# Sheet1.net
KiCad netlist of a schematic drawn in Altium Designer
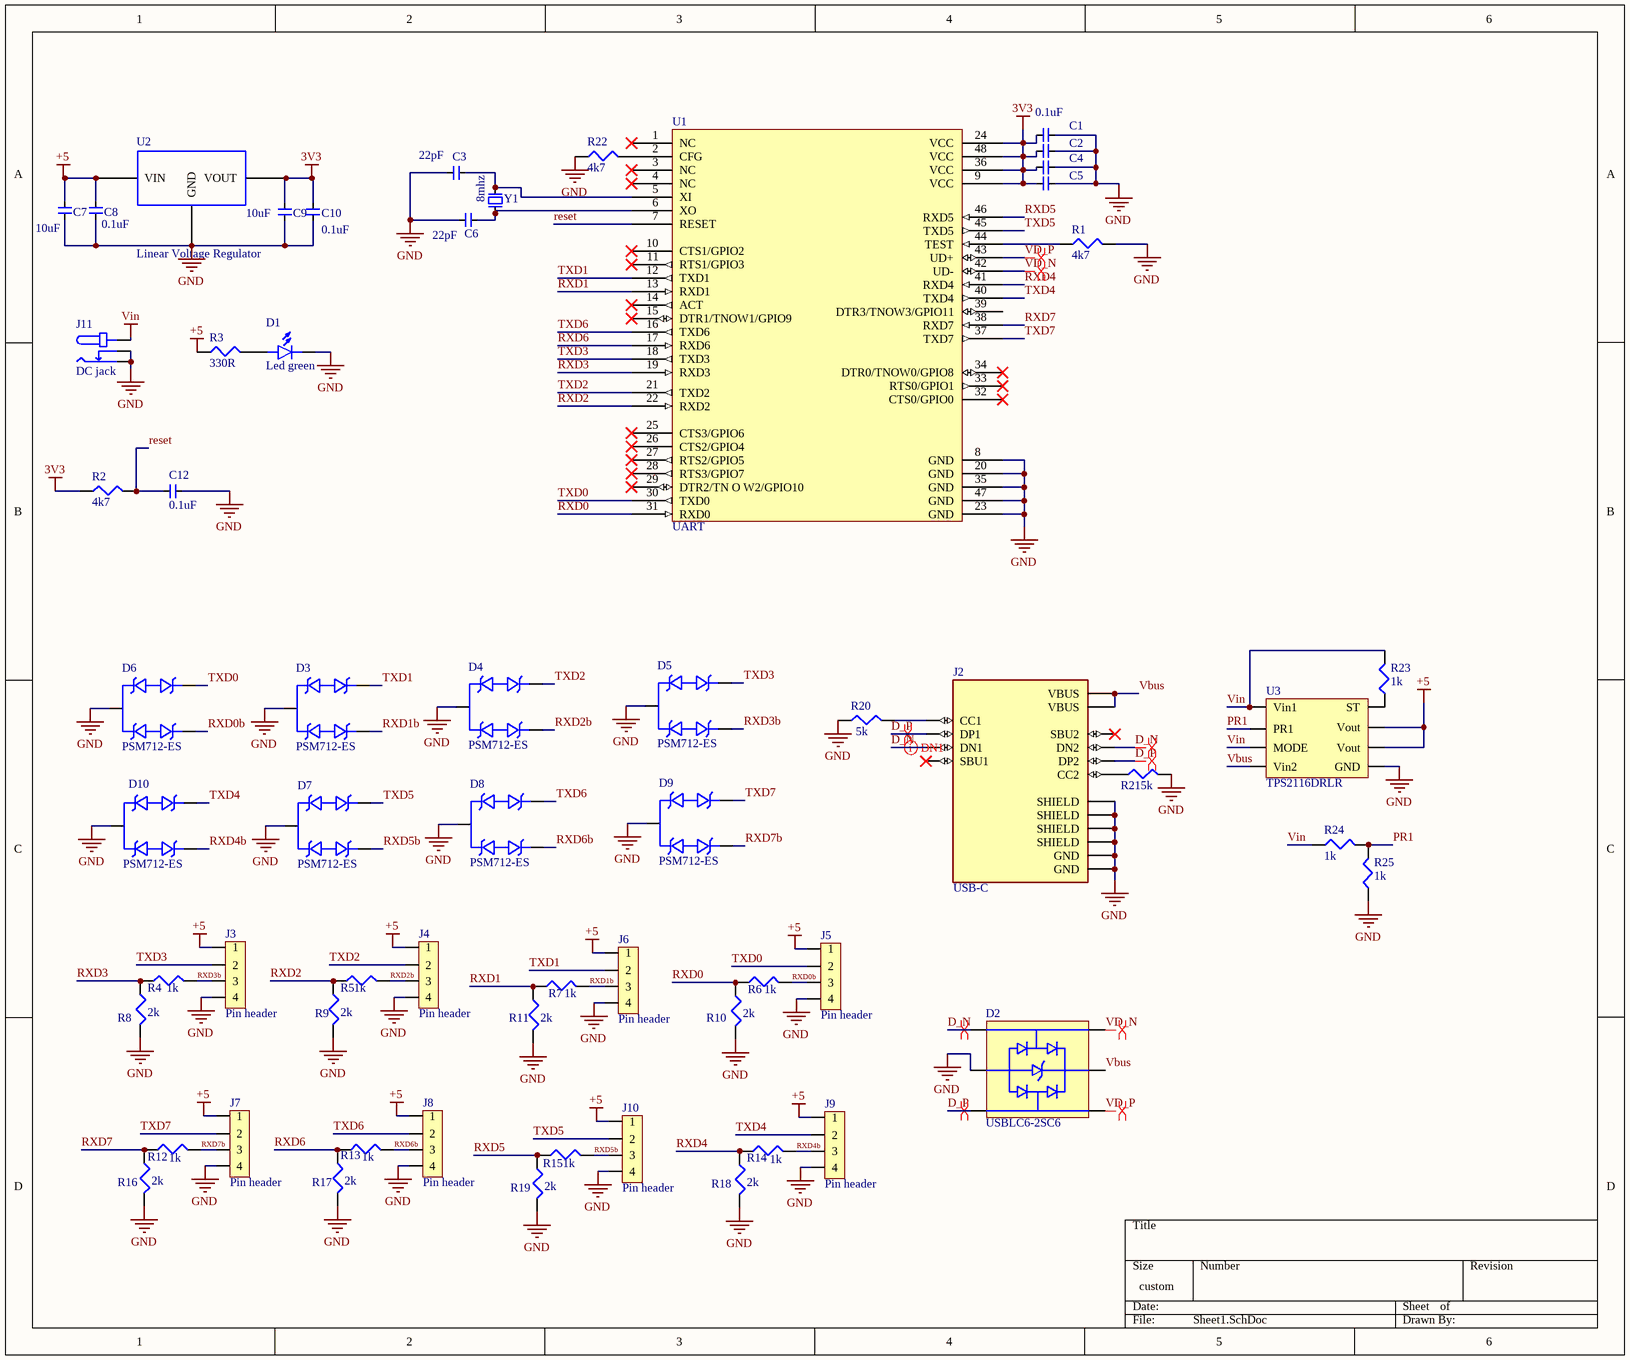
[diagram p0: Sheet1.SchDoc]

(export (version "E")
  (design (tool "Eeschema 10.0.6"))
  (components
    (comp (ref "C1")
      (value "0.1uF")
      (footprint "0603 cap")
      (description "50V 100nF X7R ±10% 0603 Multilayer Ceramic Capacitors MLCC - SMD/SMT ROHS")
      (fields
        (field (name "MANUFACTURER") "PSA(Prosperity Dielectrics)")
        (field (name "MFR. PART #") "FN18X104K500PBG")
      )
      (libsource (lib "Schlib1") (part "100nF capacitor"))
    )
    (comp (ref "C2")
      (value "100nF capacitor")
      (footprint "0603 cap")
      (description "50V 100nF X7R ±10% 0603 Multilayer Ceramic Capacitors MLCC - SMD/SMT ROHS")
      (fields
        (field (name "MANUFACTURER") "PSA(Prosperity Dielectrics)")
        (field (name "MFR. PART #") "FN18X104K500PBG")
      )
      (libsource (lib "Schlib1") (part "100nF capacitor"))
    )
    (comp (ref "C3")
      (value "22pF")
      (footprint "0603 cap")
      (description "50V 22pF C0G ±5% 0603 Multilayer Ceramic Capacitors MLCC - SMD/SMT ROHS")
      (fields
        (field (name "MANUFACTURER") "PSA(Prosperity Dielectrics)")
        (field (name "MFR. PART #") "FN18N220J500PSG")
      )
      (libsource (lib "Schlib1") (part "22pF capacitor"))
    )
    (comp (ref "C4")
      (value "100nF capacitor")
      (footprint "0603 cap")
      (description "50V 100nF X7R ±10% 0603 Multilayer Ceramic Capacitors MLCC - SMD/SMT ROHS")
      (fields
        (field (name "MANUFACTURER") "PSA(Prosperity Dielectrics)")
        (field (name "MFR. PART #") "FN18X104K500PBG")
      )
      (libsource (lib "Schlib1") (part "100nF capacitor"))
    )
    (comp (ref "C5")
      (value "100nF capacitor")
      (footprint "0603 cap")
      (description "50V 100nF X7R ±10% 0603 Multilayer Ceramic Capacitors MLCC - SMD/SMT ROHS")
      (fields
        (field (name "MANUFACTURER") "PSA(Prosperity Dielectrics)")
        (field (name "MFR. PART #") "FN18X104K500PBG")
      )
      (libsource (lib "Schlib1") (part "100nF capacitor"))
    )
    (comp (ref "C6")
      (value "22pF")
      (footprint "0603 cap")
      (description "50V 22pF C0G ±5% 0603 Multilayer Ceramic Capacitors MLCC - SMD/SMT ROHS")
      (fields
        (field (name "MANUFACTURER") "PSA(Prosperity Dielectrics)")
        (field (name "MFR. PART #") "FN18N220J500PSG")
      )
      (libsource (lib "Schlib1") (part "22pF capacitor"))
    )
    (comp (ref "C7")
      (value "10uF")
      (footprint "0603 cap")
      (description "6.3V 10uF ±10% 0603 Multilayer Ceramic Capacitors MLCC - SMD/SMT ROHS")
      (fields
        (field (name "MANUFACTURER") "PSA(Prosperity Dielectrics)")
        (field (name "MFR. PART #") "FS18B106K6R3PBG")
      )
      (libsource (lib "Schlib1") (part "10uF capacitor"))
    )
    (comp (ref "C8")
      (value "0.1uF")
      (footprint "0603 cap")
      (description "50V 100nF X7R ±10% 0603 Multilayer Ceramic Capacitors MLCC - SMD/SMT ROHS")
      (fields
        (field (name "MANUFACTURER") "PSA(Prosperity Dielectrics)")
        (field (name "MFR. PART #") "FN18X104K500PBG")
      )
      (libsource (lib "Schlib1") (part "100nF capacitor"))
    )
    (comp (ref "C9")
      (value "10uF")
      (footprint "0603 cap")
      (description "6.3V 10uF ±10% 0603 Multilayer Ceramic Capacitors MLCC - SMD/SMT ROHS")
      (fields
        (field (name "MANUFACTURER") "PSA(Prosperity Dielectrics)")
        (field (name "MFR. PART #") "FS18B106K6R3PBG")
      )
      (libsource (lib "Schlib1") (part "10uF capacitor"))
    )
    (comp (ref "C10")
      (value "0.1uF")
      (footprint "0603 cap")
      (description "50V 100nF X7R ±10% 0603 Multilayer Ceramic Capacitors MLCC - SMD/SMT ROHS")
      (fields
        (field (name "MANUFACTURER") "PSA(Prosperity Dielectrics)")
        (field (name "MFR. PART #") "FN18X104K500PBG")
      )
      (libsource (lib "Schlib1") (part "100nF capacitor"))
    )
    (comp (ref "C12")
      (value "0.1uF")
      (footprint "0603 cap")
      (description "50V 100nF X7R ±10% 0603 Multilayer Ceramic Capacitors MLCC - SMD/SMT ROHS")
      (fields
        (field (name "MANUFACTURER") "PSA(Prosperity Dielectrics)")
        (field (name "MFR. PART #") "FN18X104K500PBG")
      )
      (libsource (lib "Schlib1") (part "100nF capacitor"))
    )
    (comp (ref "D1")
      (value "Led green")
      (footprint "0805led")
      (description "Emerald 0805 Light Emitting Diodes (LED) ROHS")
      (fields (field (name "MANUFACTURER") "Yongyu Photoelectric") (field (name "MFR. PART #") "SZYY0805G"))
      (libsource (lib "Schlib1") (part "Led green"))
    )
    (comp (ref "D2")
      (value "USBLC6-2SC6")
      (footprint "SOP23-6l")
      (description "5A 17V 6V Unidirectional 5.25V SOT-23-6 Electrostatic and Surge Protection (TVS/ESD) ROHS")
      (fields (field (name "MANUFACTURER") "STMicroelectronics") (field (name "LCSC PART #") "C7519"))
      (libsource (lib "Schlib1") (part "USBLC6-2SC6"))
    )
    (comp (ref "D3")
      (value "PSM712-ES")
      (footprint "sop23")
      (description "17A 350W Bi-Directional SOT-23 Electrostatic and Surge Protection (TVS/ESD) ROHS")
      (fields (field (name "MANUFACTURER") "ElecSuper") (field (name "LCSC PART #") "C5180294"))
      (libsource (lib "Schlib1") (part "PSM712-ES"))
    )
    (comp (ref "D4")
      (value "PSM712-ES")
      (footprint "sop23")
      (description "17A 350W Bi-Directional SOT-23 Electrostatic and Surge Protection (TVS/ESD) ROHS")
      (fields (field (name "MANUFACTURER") "ElecSuper") (field (name "LCSC PART #") "C5180294"))
      (libsource (lib "Schlib1") (part "PSM712-ES"))
    )
    (comp (ref "D5")
      (value "PSM712-ES")
      (footprint "sop23")
      (description "17A 350W Bi-Directional SOT-23 Electrostatic and Surge Protection (TVS/ESD) ROHS")
      (fields (field (name "MANUFACTURER") "ElecSuper") (field (name "LCSC PART #") "C5180294"))
      (libsource (lib "Schlib1") (part "PSM712-ES"))
    )
    (comp (ref "D6")
      (value "PSM712-ES")
      (footprint "sop23")
      (description "17A 350W Bi-Directional SOT-23 Electrostatic and Surge Protection (TVS/ESD) ROHS")
      (fields (field (name "MANUFACTURER") "ElecSuper") (field (name "LCSC PART #") "C5180294"))
      (libsource (lib "Schlib1") (part "PSM712-ES"))
    )
    (comp (ref "D7")
      (value "PSM712-ES")
      (footprint "sop23")
      (description "17A 350W Bi-Directional SOT-23 Electrostatic and Surge Protection (TVS/ESD) ROHS")
      (fields (field (name "MANUFACTURER") "ElecSuper") (field (name "LCSC PART #") "C5180294"))
      (libsource (lib "Schlib1") (part "PSM712-ES"))
    )
    (comp (ref "D8")
      (value "PSM712-ES")
      (footprint "sop23")
      (description "17A 350W Bi-Directional SOT-23 Electrostatic and Surge Protection (TVS/ESD) ROHS")
      (fields (field (name "MANUFACTURER") "ElecSuper") (field (name "LCSC PART #") "C5180294"))
      (libsource (lib "Schlib1") (part "PSM712-ES"))
    )
    (comp (ref "D9")
      (value "PSM712-ES")
      (footprint "sop23")
      (description "17A 350W Bi-Directional SOT-23 Electrostatic and Surge Protection (TVS/ESD) ROHS")
      (fields (field (name "MANUFACTURER") "ElecSuper") (field (name "LCSC PART #") "C5180294"))
      (libsource (lib "Schlib1") (part "PSM712-ES"))
    )
    (comp (ref "D10")
      (value "PSM712-ES")
      (footprint "sop23")
      (description "17A 350W Bi-Directional SOT-23 Electrostatic and Surge Protection (TVS/ESD) ROHS")
      (fields (field (name "MANUFACTURER") "ElecSuper") (field (name "LCSC PART #") "C5180294"))
      (libsource (lib "Schlib1") (part "PSM712-ES"))
    )
    (comp (ref "J2")
      (value "USB-C")
      (footprint "USB-C")
      (description "5A 1 16P Female Type-C SMD USB Connectors ROHS")
      (fields
        (field (name "MANUFACTURER") "Korean Hroparts Elec")
        (field (name "MFR. PART #") "TYPE-C-31-M-12")
      )
      (libsource (lib "Schlib1") (part "USB-C"))
    )
    (comp (ref "J3")
      (value "Pin header")
      (footprint "jst 4 pin")
      (description "1x4P 4P XH 1 2.5mm 4 Phosphor bronze Plugin,P=2.5mm Wire To Board Connector ROHS")
      (fields (field (name "MANUFACTURER") "BOOMELE") (field (name "MFR. PART #") "XH-4A"))
      (libsource (lib "Schlib1") (part "Pin header"))
    )
    (comp (ref "J4")
      (value "Pin header")
      (footprint "jst 4 pin")
      (description "1x4P 4P XH 1 2.5mm 4 Phosphor bronze Plugin,P=2.5mm Wire To Board Connector ROHS")
      (fields (field (name "MANUFACTURER") "BOOMELE") (field (name "MFR. PART #") "XH-4A"))
      (libsource (lib "Schlib1") (part "Pin header"))
    )
    (comp (ref "J5")
      (value "Pin header")
      (footprint "jst 4 pin")
      (description "1x4P 4P XH 1 2.5mm 4 Phosphor bronze Plugin,P=2.5mm Wire To Board Connector ROHS")
      (fields (field (name "MANUFACTURER") "BOOMELE") (field (name "MFR. PART #") "XH-4A"))
      (libsource (lib "Schlib1") (part "Pin header"))
    )
    (comp (ref "J6")
      (value "Pin header")
      (footprint "jst 4 pin")
      (description "1x4P 4P XH 1 2.5mm 4 Phosphor bronze Plugin,P=2.5mm Wire To Board Connector ROHS")
      (fields (field (name "MANUFACTURER") "BOOMELE") (field (name "MFR. PART #") "XH-4A"))
      (libsource (lib "Schlib1") (part "Pin header"))
    )
    (comp (ref "J7")
      (value "Pin header")
      (footprint "jst 4 pin")
      (description "1x4P 4P XH 1 2.5mm 4 Phosphor bronze Plugin,P=2.5mm Wire To Board Connector ROHS")
      (fields (field (name "MANUFACTURER") "BOOMELE") (field (name "MFR. PART #") "XH-4A"))
      (libsource (lib "Schlib1") (part "Pin header"))
    )
    (comp (ref "J8")
      (value "Pin header")
      (footprint "jst 4 pin")
      (description "1x4P 4P XH 1 2.5mm 4 Phosphor bronze Plugin,P=2.5mm Wire To Board Connector ROHS")
      (fields (field (name "MANUFACTURER") "BOOMELE") (field (name "MFR. PART #") "XH-4A"))
      (libsource (lib "Schlib1") (part "Pin header"))
    )
    (comp (ref "J9")
      (value "Pin header")
      (footprint "jst 4 pin")
      (description "1x4P 4P XH 1 2.5mm 4 Phosphor bronze Plugin,P=2.5mm Wire To Board Connector ROHS")
      (fields (field (name "MANUFACTURER") "BOOMELE") (field (name "MFR. PART #") "XH-4A"))
      (libsource (lib "Schlib1") (part "Pin header"))
    )
    (comp (ref "J10")
      (value "Pin header")
      (footprint "jst 4 pin")
      (description "1x4P 4P XH 1 2.5mm 4 Phosphor bronze Plugin,P=2.5mm Wire To Board Connector ROHS")
      (fields (field (name "MANUFACTURER") "BOOMELE") (field (name "MFR. PART #") "XH-4A"))
      (libsource (lib "Schlib1") (part "Pin header"))
    )
    (comp (ref "J11")
      (value "DC jack")
      (footprint "DC jack")
      (fields
        (field (name "MANUFACTURER") "XKB Connection")
        (field (name "MFR. PART #") "DC-005-2.5A-2.0")
        (field (name "LCSC PART #") "C319099")
      )
      (libsource (lib "Schlib1") (part "DC jack"))
    )
    (comp (ref "R1")
      (value "4k7")
      (footprint "0603 cap")
      (description "100mW Thick Film Resistors 75V ±100ppm/℃ ±5% 4.7kΩ 0603 Chip Resistor - Surface Mount ROHS")
      (fields
        (field (name "MANUFACTURER") "UNI-ROYAL(Uniroyal Elec)")
        (field (name "MFR. PART #") "0603WAJ0472T5E")
      )
      (libsource (lib "Schlib1") (part "4k7 resistor"))
    )
    (comp (ref "R2")
      (value "4k7")
      (footprint "0603 cap")
      (description "100mW Thick Film Resistors 75V ±100ppm/℃ ±5% 4.7kΩ 0603 Chip Resistor - Surface Mount ROHS")
      (fields
        (field (name "MANUFACTURER") "UNI-ROYAL(Uniroyal Elec)")
        (field (name "MFR. PART #") "0603WAJ0472T5E")
      )
      (libsource (lib "Schlib1") (part "4k7 resistor"))
    )
    (comp (ref "R3")
      (value "330R")
      (footprint "0603 cap")
      (description "100mW Thick Film Resistors 75V ±100ppm/℃ ±1% 330Ω 0603 Chip Resistor - Surface Mount ROHS")
      (fields
        (field (name "MANUFACTURER") "UNI-ROYAL(Uniroyal Elec)")
        (field (name "MFR. PART #") "0603WAF3300T5E")
      )
      (libsource (lib "Schlib1") (part "330R"))
    )
    (comp (ref "R4")
      (value "1k")
      (footprint "0603 cap")
      (description "100mW Thick Film Resistors 75V ±100ppm/℃ ±1% 1kΩ 0603 Chip Resistor - Surface Mount ROHS")
      (fields
        (field (name "MANUFACTURER") "UNI-ROYAL(Uniroyal Elec)")
        (field (name "MFR. PART #") "0603WAF1001T5E")
      )
      (libsource (lib "Schlib1") (part "1k resistor"))
    )
    (comp (ref "R5")
      (value "1k")
      (footprint "0603 cap")
      (description "100mW Thick Film Resistors 75V ±100ppm/℃ ±1% 1kΩ 0603 Chip Resistor - Surface Mount ROHS")
      (fields
        (field (name "MANUFACTURER") "UNI-ROYAL(Uniroyal Elec)")
        (field (name "MFR. PART #") "0603WAF1001T5E")
      )
      (libsource (lib "Schlib1") (part "1k resistor"))
    )
    (comp (ref "R6")
      (value "1k")
      (footprint "0603 cap")
      (description "100mW Thick Film Resistors 75V ±100ppm/℃ ±1% 1kΩ 0603 Chip Resistor - Surface Mount ROHS")
      (fields
        (field (name "MANUFACTURER") "UNI-ROYAL(Uniroyal Elec)")
        (field (name "MFR. PART #") "0603WAF1001T5E")
      )
      (libsource (lib "Schlib1") (part "1k resistor"))
    )
    (comp (ref "R7")
      (value "1k")
      (footprint "0603 cap")
      (description "100mW Thick Film Resistors 75V ±100ppm/℃ ±1% 1kΩ 0603 Chip Resistor - Surface Mount ROHS")
      (fields
        (field (name "MANUFACTURER") "UNI-ROYAL(Uniroyal Elec)")
        (field (name "MFR. PART #") "0603WAF1001T5E")
      )
      (libsource (lib "Schlib1") (part "1k resistor"))
    )
    (comp (ref "R8")
      (value "2k")
      (footprint "0603 cap")
      (description "100mW Thick Film Resistors 75V ±100ppm/℃ ±1% 2kΩ 0603 Chip Resistor - Surface Mount ROHS")
      (fields
        (field (name "MANUFACTURER") "UNI-ROYAL(Uniroyal Elec)")
        (field (name "MFR. PART #") "0603WAF2001T5E")
      )
      (libsource (lib "Schlib1") (part "2k resistor"))
    )
    (comp (ref "R9")
      (value "2k")
      (footprint "0603 cap")
      (description "100mW Thick Film Resistors 75V ±100ppm/℃ ±1% 2kΩ 0603 Chip Resistor - Surface Mount ROHS")
      (fields
        (field (name "MANUFACTURER") "UNI-ROYAL(Uniroyal Elec)")
        (field (name "MFR. PART #") "0603WAF2001T5E")
      )
      (libsource (lib "Schlib1") (part "2k resistor"))
    )
    (comp (ref "R10")
      (value "2k")
      (footprint "0603 cap")
      (description "100mW Thick Film Resistors 75V ±100ppm/℃ ±1% 2kΩ 0603 Chip Resistor - Surface Mount ROHS")
      (fields
        (field (name "MANUFACTURER") "UNI-ROYAL(Uniroyal Elec)")
        (field (name "MFR. PART #") "0603WAF2001T5E")
      )
      (libsource (lib "Schlib1") (part "2k resistor"))
    )
    (comp (ref "R11")
      (value "2k")
      (footprint "0603 cap")
      (description "100mW Thick Film Resistors 75V ±100ppm/℃ ±1% 2kΩ 0603 Chip Resistor - Surface Mount ROHS")
      (fields
        (field (name "MANUFACTURER") "UNI-ROYAL(Uniroyal Elec)")
        (field (name "MFR. PART #") "0603WAF2001T5E")
      )
      (libsource (lib "Schlib1") (part "2k resistor"))
    )
    (comp (ref "R12")
      (value "1k")
      (footprint "0603 cap")
      (description "100mW Thick Film Resistors 75V ±100ppm/℃ ±1% 1kΩ 0603 Chip Resistor - Surface Mount ROHS")
      (fields
        (field (name "MANUFACTURER") "UNI-ROYAL(Uniroyal Elec)")
        (field (name "MFR. PART #") "0603WAF1001T5E")
      )
      (libsource (lib "Schlib1") (part "1k resistor"))
    )
    (comp (ref "R13")
      (value "1k")
      (footprint "0603 cap")
      (description "100mW Thick Film Resistors 75V ±100ppm/℃ ±1% 1kΩ 0603 Chip Resistor - Surface Mount ROHS")
      (fields
        (field (name "MANUFACTURER") "UNI-ROYAL(Uniroyal Elec)")
        (field (name "MFR. PART #") "0603WAF1001T5E")
      )
      (libsource (lib "Schlib1") (part "1k resistor"))
    )
    (comp (ref "R14")
      (value "1k")
      (footprint "0603 cap")
      (description "100mW Thick Film Resistors 75V ±100ppm/℃ ±1% 1kΩ 0603 Chip Resistor - Surface Mount ROHS")
      (fields
        (field (name "MANUFACTURER") "UNI-ROYAL(Uniroyal Elec)")
        (field (name "MFR. PART #") "0603WAF1001T5E")
      )
      (libsource (lib "Schlib1") (part "1k resistor"))
    )
    (comp (ref "R15")
      (value "1k")
      (footprint "0603 cap")
      (description "100mW Thick Film Resistors 75V ±100ppm/℃ ±1% 1kΩ 0603 Chip Resistor - Surface Mount ROHS")
      (fields
        (field (name "MANUFACTURER") "UNI-ROYAL(Uniroyal Elec)")
        (field (name "MFR. PART #") "0603WAF1001T5E")
      )
      (libsource (lib "Schlib1") (part "1k resistor"))
    )
    (comp (ref "R16")
      (value "2k")
      (footprint "0603 cap")
      (description "100mW Thick Film Resistors 75V ±100ppm/℃ ±1% 2kΩ 0603 Chip Resistor - Surface Mount ROHS")
      (fields
        (field (name "MANUFACTURER") "UNI-ROYAL(Uniroyal Elec)")
        (field (name "MFR. PART #") "0603WAF2001T5E")
      )
      (libsource (lib "Schlib1") (part "2k resistor"))
    )
    (comp (ref "R17")
      (value "2k")
      (footprint "0603 cap")
      (description "100mW Thick Film Resistors 75V ±100ppm/℃ ±1% 2kΩ 0603 Chip Resistor - Surface Mount ROHS")
      (fields
        (field (name "MANUFACTURER") "UNI-ROYAL(Uniroyal Elec)")
        (field (name "MFR. PART #") "0603WAF2001T5E")
      )
      (libsource (lib "Schlib1") (part "2k resistor"))
    )
    (comp (ref "R18")
      (value "2k")
      (footprint "0603 cap")
      (description "100mW Thick Film Resistors 75V ±100ppm/℃ ±1% 2kΩ 0603 Chip Resistor - Surface Mount ROHS")
      (fields
        (field (name "MANUFACTURER") "UNI-ROYAL(Uniroyal Elec)")
        (field (name "MFR. PART #") "0603WAF2001T5E")
      )
      (libsource (lib "Schlib1") (part "2k resistor"))
    )
    (comp (ref "R19")
      (value "2k")
      (footprint "0603 cap")
      (description "100mW Thick Film Resistors 75V ±100ppm/℃ ±1% 2kΩ 0603 Chip Resistor - Surface Mount ROHS")
      (fields
        (field (name "MANUFACTURER") "UNI-ROYAL(Uniroyal Elec)")
        (field (name "MFR. PART #") "0603WAF2001T5E")
      )
      (libsource (lib "Schlib1") (part "2k resistor"))
    )
    (comp (ref "R20")
      (value "5k")
      (footprint "0603 cap")
      (description "100mW Thick Film Resistors 75V ±100ppm/℃ ±1% 330Ω 0603 Chip Resistor - Surface Mount ROHS")
      (fields
        (field (name "MANUFACTURER") "UNI-ROYAL(Uniroyal Elec)")
        (field (name "MFR. PART #") "0603WAF5101T5E")
      )
      (libsource (lib "Schlib1") (part "5k"))
    )
    (comp (ref "R21")
      (value "5k")
      (footprint "0603 cap")
      (description "100mW Thick Film Resistors 75V ±100ppm/℃ ±1% 330Ω 0603 Chip Resistor - Surface Mount ROHS")
      (fields
        (field (name "MANUFACTURER") "UNI-ROYAL(Uniroyal Elec)")
        (field (name "MFR. PART #") "0603WAF5101T5E")
      )
      (libsource (lib "Schlib1") (part "5k"))
    )
    (comp (ref "R22")
      (value "4k7")
      (footprint "0603 cap")
      (description "100mW Thick Film Resistors 75V ±100ppm/℃ ±5% 4.7kΩ 0603 Chip Resistor - Surface Mount ROHS")
      (fields
        (field (name "MANUFACTURER") "UNI-ROYAL(Uniroyal Elec)")
        (field (name "MFR. PART #") "0603WAJ0472T5E")
      )
      (libsource (lib "Schlib1") (part "4k7 resistor"))
    )
    (comp (ref "R23")
      (value "1k")
      (footprint "0603 cap")
      (description "100mW Thick Film Resistors 75V ±100ppm/℃ ±1% 1kΩ 0603 Chip Resistor - Surface Mount ROHS")
      (fields
        (field (name "MANUFACTURER") "UNI-ROYAL(Uniroyal Elec)")
        (field (name "MFR. PART #") "0603WAF1001T5E")
      )
      (libsource (lib "Schlib1") (part "1k resistor"))
    )
    (comp (ref "R24")
      (value "1k")
      (footprint "0603 cap")
      (description "100mW Thick Film Resistors 75V ±100ppm/℃ ±1% 1kΩ 0603 Chip Resistor - Surface Mount ROHS")
      (fields
        (field (name "MANUFACTURER") "UNI-ROYAL(Uniroyal Elec)")
        (field (name "MFR. PART #") "0603WAF1001T5E")
      )
      (libsource (lib "Schlib1") (part "1k resistor"))
    )
    (comp (ref "R25")
      (value "1k")
      (footprint "0603 cap")
      (description "100mW Thick Film Resistors 75V ±100ppm/℃ ±1% 1kΩ 0603 Chip Resistor - Surface Mount ROHS")
      (fields
        (field (name "MANUFACTURER") "UNI-ROYAL(Uniroyal Elec)")
        (field (name "MFR. PART #") "0603WAF1001T5E")
      )
      (libsource (lib "Schlib1") (part "1k resistor"))
    )
    (comp (ref "U1")
      (value "UART")
      (footprint "UART")
      (description "LQFP-48(7x7) USB ICs ROHS")
      (fields
        (field (name "MANUFACTURER") "WCH(Jiangsu Qin Heng)")
        (field (name "MANUFACTURER PART NUMBER") "CH348Q")
      )
      (libsource (lib "Schlib1") (part "UART"))
    )
    (comp (ref "U2")
      (value "Linear Voltage Regulator")
      (footprint "linear voltage regulato")
      (description "SOT-223 Linear Voltage Regulators (LDO) ROHS")
      (fields (field (name "MANUFACTURER") "IDCHIP") (field (name "MANUFACTURER PART NUMBER") "1117-5"))
      (libsource (lib "Schlib1") (part "Linear Voltage Regulator"))
    )
    (comp (ref "U3")
      (value "TPS2116DRLR")
      (footprint "SOP8")
      (description "1.6V~5.5V 42mΩ 2.5A 1 SOT-583 Power Distribution Switches ROHS")
      (fields (field (name "MANUFACTURER") "Texas Instruments") (field (name "LCSC PART #") "C3235557"))
      (libsource (lib "Schlib1") (part "TPS2116DRLR"))
    )
    (comp (ref "Y1")
      (value "8mhz")
      (footprint "crystal")
      (description "8MHz 贴片晶振 20pF ±20ppm ±20ppm HC-49S-SMD Crystals ROHS")
      (fields (field (name "MANUFACTURER") "KYX") (field (name "MFR. PART #") "KBD080002020"))
      (libsource (lib "Schlib1") (part "Crystal 8mhz"))
    )
  )
  (nets
    (net (code "1") (name "+5") (class "Default")
      (node (ref "C7") (pin "2") (pinfunction "2_2") (pintype "passive"))
      (node (ref "C8") (pin "2") (pinfunction "2_2") (pintype "passive"))
      (node (ref "J10") (pin "1") (pinfunction "1_1") (pintype "passive"))
      (node (ref "J3") (pin "1") (pinfunction "1_1") (pintype "passive"))
      (node (ref "J4") (pin "1") (pinfunction "1_1") (pintype "passive"))
      (node (ref "J5") (pin "1") (pinfunction "1_1") (pintype "passive"))
      (node (ref "J6") (pin "1") (pinfunction "1_1") (pintype "passive"))
      (node (ref "J7") (pin "1") (pinfunction "1_1") (pintype "passive"))
      (node (ref "J8") (pin "1") (pinfunction "1_1") (pintype "passive"))
      (node (ref "J9") (pin "1") (pinfunction "1_1") (pintype "passive"))
      (node (ref "R3") (pin "1") (pinfunction "1_1") (pintype "passive"))
      (node (ref "U2") (pin "3") (pinfunction "VIN_3") (pintype "passive"))
      (node (ref "U3") (pin "2") (pinfunction "Vout_2") (pintype "passive"))
      (node (ref "U3") (pin "7") (pinfunction "Vout_7") (pintype "passive"))
    )
    (net (code "2") (name "/D_N") (class "Default")
      (node (ref "D2") (pin "1") (pinfunction "I/O_1_1") (pintype "passive"))
      (node (ref "J2") (pin "A7") (pinfunction "DN1_A7") (pintype "bidirectional"))
      (node (ref "J2") (pin "B7") (pinfunction "DN2_B7") (pintype "bidirectional"))
    )
    (net (code "3") (name "/D_P") (class "Default")
      (node (ref "D2") (pin "3") (pinfunction "I/O_2_3") (pintype "passive"))
      (node (ref "J2") (pin "A6") (pinfunction "DP1_A6") (pintype "bidirectional"))
      (node (ref "J2") (pin "B6") (pinfunction "DP2_B6") (pintype "bidirectional"))
    )
    (net (code "4") (name "/PR1") (class "Default")
      (node (ref "R24") (pin "2") (pinfunction "2_2") (pintype "passive"))
      (node (ref "R25") (pin "2") (pinfunction "2_2") (pintype "passive"))
      (node (ref "U3") (pin "4") (pinfunction "PR1_4") (pintype "passive"))
    )
    (net (code "5") (name "/RXD0") (class "Default")
      (node (ref "R10") (pin "1") (pinfunction "1_1") (pintype "passive"))
      (node (ref "R6") (pin "1") (pinfunction "1_1") (pintype "passive"))
      (node (ref "U1") (pin "31") (pinfunction "RXD0_31") (pintype "input"))
    )
    (net (code "6") (name "/RXD0b") (class "Default")
      (node (ref "D6") (pin "1") (pinfunction "1_1") (pintype "passive"))
      (node (ref "J5") (pin "3") (pinfunction "3_3") (pintype "passive"))
      (node (ref "R6") (pin "2") (pinfunction "2_2") (pintype "passive"))
    )
    (net (code "7") (name "/RXD1") (class "Default")
      (node (ref "R11") (pin "1") (pinfunction "1_1") (pintype "passive"))
      (node (ref "R7") (pin "1") (pinfunction "1_1") (pintype "passive"))
      (node (ref "U1") (pin "13") (pinfunction "RXD1_13") (pintype "input"))
    )
    (net (code "8") (name "/RXD1b") (class "Default")
      (node (ref "D3") (pin "1") (pinfunction "1_1") (pintype "passive"))
      (node (ref "J6") (pin "3") (pinfunction "3_3") (pintype "passive"))
      (node (ref "R7") (pin "2") (pinfunction "2_2") (pintype "passive"))
    )
    (net (code "9") (name "/RXD2") (class "Default")
      (node (ref "R5") (pin "1") (pinfunction "1_1") (pintype "passive"))
      (node (ref "R9") (pin "1") (pinfunction "1_1") (pintype "passive"))
      (node (ref "U1") (pin "22") (pinfunction "RXD2_22") (pintype "input"))
    )
    (net (code "10") (name "/RXD2b") (class "Default")
      (node (ref "D4") (pin "1") (pinfunction "1_1") (pintype "passive"))
      (node (ref "J4") (pin "3") (pinfunction "3_3") (pintype "passive"))
      (node (ref "R5") (pin "2") (pinfunction "2_2") (pintype "passive"))
    )
    (net (code "11") (name "/RXD3") (class "Default")
      (node (ref "R4") (pin "1") (pinfunction "1_1") (pintype "passive"))
      (node (ref "R8") (pin "1") (pinfunction "1_1") (pintype "passive"))
      (node (ref "U1") (pin "19") (pinfunction "RXD3_19") (pintype "input"))
    )
    (net (code "12") (name "/RXD3b") (class "Default")
      (node (ref "D5") (pin "1") (pinfunction "1_1") (pintype "passive"))
      (node (ref "J3") (pin "3") (pinfunction "3_3") (pintype "passive"))
      (node (ref "R4") (pin "2") (pinfunction "2_2") (pintype "passive"))
    )
    (net (code "13") (name "/RXD4") (class "Default")
      (node (ref "R14") (pin "1") (pinfunction "1_1") (pintype "passive"))
      (node (ref "R18") (pin "1") (pinfunction "1_1") (pintype "passive"))
      (node (ref "U1") (pin "41") (pinfunction "RXD4_41") (pintype "input"))
    )
    (net (code "14") (name "/RXD4b") (class "Default")
      (node (ref "D10") (pin "1") (pinfunction "1_1") (pintype "passive"))
      (node (ref "J9") (pin "3") (pinfunction "3_3") (pintype "passive"))
      (node (ref "R14") (pin "2") (pinfunction "2_2") (pintype "passive"))
    )
    (net (code "15") (name "/RXD5") (class "Default")
      (node (ref "R15") (pin "1") (pinfunction "1_1") (pintype "passive"))
      (node (ref "R19") (pin "1") (pinfunction "1_1") (pintype "passive"))
      (node (ref "U1") (pin "46") (pinfunction "RXD5_46") (pintype "input"))
    )
    (net (code "16") (name "/RXD5b") (class "Default")
      (node (ref "D7") (pin "1") (pinfunction "1_1") (pintype "passive"))
      (node (ref "J10") (pin "3") (pinfunction "3_3") (pintype "passive"))
      (node (ref "R15") (pin "2") (pinfunction "2_2") (pintype "passive"))
    )
    (net (code "17") (name "/RXD6") (class "Default")
      (node (ref "R13") (pin "1") (pinfunction "1_1") (pintype "passive"))
      (node (ref "R17") (pin "1") (pinfunction "1_1") (pintype "passive"))
      (node (ref "U1") (pin "17") (pinfunction "RXD6_17") (pintype "input"))
    )
    (net (code "18") (name "/RXD6b") (class "Default")
      (node (ref "D8") (pin "1") (pinfunction "1_1") (pintype "passive"))
      (node (ref "J8") (pin "3") (pinfunction "3_3") (pintype "passive"))
      (node (ref "R13") (pin "2") (pinfunction "2_2") (pintype "passive"))
    )
    (net (code "19") (name "/RXD7") (class "Default")
      (node (ref "R12") (pin "1") (pinfunction "1_1") (pintype "passive"))
      (node (ref "R16") (pin "1") (pinfunction "1_1") (pintype "passive"))
      (node (ref "U1") (pin "38") (pinfunction "RXD7_38") (pintype "input"))
    )
    (net (code "20") (name "/RXD7b") (class "Default")
      (node (ref "D9") (pin "1") (pinfunction "1_1") (pintype "passive"))
      (node (ref "J7") (pin "3") (pinfunction "3_3") (pintype "passive"))
      (node (ref "R12") (pin "2") (pinfunction "2_2") (pintype "passive"))
    )
    (net (code "21") (name "/TXD0") (class "Default")
      (node (ref "D6") (pin "2") (pinfunction "2_2") (pintype "passive"))
      (node (ref "J5") (pin "2") (pinfunction "2_2") (pintype "passive"))
      (node (ref "U1") (pin "30") (pinfunction "TXD0_30") (pintype "output"))
    )
    (net (code "22") (name "/TXD1") (class "Default")
      (node (ref "D3") (pin "2") (pinfunction "2_2") (pintype "passive"))
      (node (ref "J6") (pin "2") (pinfunction "2_2") (pintype "passive"))
      (node (ref "U1") (pin "12") (pinfunction "TXD1_12") (pintype "output"))
    )
    (net (code "23") (name "/TXD2") (class "Default")
      (node (ref "D4") (pin "2") (pinfunction "2_2") (pintype "passive"))
      (node (ref "J4") (pin "2") (pinfunction "2_2") (pintype "passive"))
      (node (ref "U1") (pin "21") (pinfunction "TXD2_21") (pintype "output"))
    )
    (net (code "24") (name "/TXD3") (class "Default")
      (node (ref "D5") (pin "2") (pinfunction "2_2") (pintype "passive"))
      (node (ref "J3") (pin "2") (pinfunction "2_2") (pintype "passive"))
      (node (ref "U1") (pin "18") (pinfunction "TXD3_18") (pintype "output"))
    )
    (net (code "25") (name "/TXD4") (class "Default")
      (node (ref "D10") (pin "2") (pinfunction "2_2") (pintype "passive"))
      (node (ref "J9") (pin "2") (pinfunction "2_2") (pintype "passive"))
      (node (ref "U1") (pin "40") (pinfunction "TXD4_40") (pintype "output"))
    )
    (net (code "26") (name "/TXD5") (class "Default")
      (node (ref "D7") (pin "2") (pinfunction "2_2") (pintype "passive"))
      (node (ref "J10") (pin "2") (pinfunction "2_2") (pintype "passive"))
      (node (ref "U1") (pin "45") (pinfunction "TXD5_45") (pintype "output"))
    )
    (net (code "27") (name "/TXD6") (class "Default")
      (node (ref "D8") (pin "2") (pinfunction "2_2") (pintype "passive"))
      (node (ref "J8") (pin "2") (pinfunction "2_2") (pintype "passive"))
      (node (ref "U1") (pin "16") (pinfunction "TXD6_16") (pintype "output"))
    )
    (net (code "28") (name "/TXD7") (class "Default")
      (node (ref "D9") (pin "2") (pinfunction "2_2") (pintype "passive"))
      (node (ref "J7") (pin "2") (pinfunction "2_2") (pintype "passive"))
      (node (ref "U1") (pin "37") (pinfunction "TXD7_37") (pintype "output"))
    )
    (net (code "29") (name "/VD_N") (class "Default")
      (node (ref "D2") (pin "6") (pinfunction "I/O_1_6") (pintype "passive"))
      (node (ref "U1") (pin "42") (pinfunction "UD-_42") (pintype "bidirectional"))
    )
    (net (code "30") (name "/VD_P") (class "Default")
      (node (ref "D2") (pin "4") (pinfunction "I/O_2_4") (pintype "passive"))
      (node (ref "U1") (pin "43") (pinfunction "UD+_43") (pintype "bidirectional"))
    )
    (net (code "31") (name "/Vbus") (class "Default")
      (node (ref "D2") (pin "5") (pinfunction "Vbus_5") (pintype "passive"))
      (node (ref "J2") (pin "A4/B9") (pinfunction "VBUS_A4/B9") (pintype "power_in"))
      (node (ref "J2") (pin "B4/A9") (pinfunction "VBUS_B4/A9") (pintype "power_in"))
      (node (ref "U3") (pin "6") (pinfunction "Vin2_6") (pintype "passive"))
    )
    (net (code "32") (name "/reset") (class "Default")
      (node (ref "C12") (pin "2") (pinfunction "2_2") (pintype "passive"))
      (node (ref "R2") (pin "2") (pinfunction "2_2") (pintype "passive"))
      (node (ref "U1") (pin "7") (pinfunction "RESET_7") (pintype "passive"))
    )
    (net (code "33") (name "3V3") (class "Default")
      (node (ref "C1") (pin "1") (pinfunction "1_1") (pintype "passive"))
      (node (ref "C10") (pin "2") (pinfunction "2_2") (pintype "passive"))
      (node (ref "C2") (pin "1") (pinfunction "1_1") (pintype "passive"))
      (node (ref "C4") (pin "1") (pinfunction "1_1") (pintype "passive"))
      (node (ref "C5") (pin "1") (pinfunction "1_1") (pintype "passive"))
      (node (ref "C9") (pin "2") (pinfunction "2_2") (pintype "passive"))
      (node (ref "R2") (pin "1") (pinfunction "1_1") (pintype "passive"))
      (node (ref "U1") (pin "24") (pinfunction "VCC_24") (pintype "power_in"))
      (node (ref "U1") (pin "36") (pinfunction "VCC_36") (pintype "power_in"))
      (node (ref "U1") (pin "48") (pinfunction "VCC_48") (pintype "power_in"))
      (node (ref "U1") (pin "9") (pinfunction "VCC_9") (pintype "power_in"))
      (node (ref "U2") (pin "2") (pinfunction "VOUT_2") (pintype "passive"))
    )
    (net (code "34") (name "GND") (class "Default")
      (node (ref "C1") (pin "2") (pinfunction "2_2") (pintype "passive"))
      (node (ref "C10") (pin "1") (pinfunction "1_1") (pintype "passive"))
      (node (ref "C12") (pin "1") (pinfunction "1_1") (pintype "passive"))
      (node (ref "C2") (pin "2") (pinfunction "2_2") (pintype "passive"))
      (node (ref "C3") (pin "1") (pinfunction "1_1") (pintype "passive"))
      (node (ref "C4") (pin "2") (pinfunction "2_2") (pintype "passive"))
      (node (ref "C5") (pin "2") (pinfunction "2_2") (pintype "passive"))
      (node (ref "C6") (pin "1") (pinfunction "1_1") (pintype "passive"))
      (node (ref "C7") (pin "1") (pinfunction "1_1") (pintype "passive"))
      (node (ref "C8") (pin "1") (pinfunction "1_1") (pintype "passive"))
      (node (ref "C9") (pin "1") (pinfunction "1_1") (pintype "passive"))
      (node (ref "D1") (pin "2") (pinfunction "2_2") (pintype "passive"))
      (node (ref "D10") (pin "3") (pinfunction "3_3") (pintype "passive"))
      (node (ref "D2") (pin "2") (pinfunction "GND_2") (pintype "passive"))
      (node (ref "D3") (pin "3") (pinfunction "3_3") (pintype "passive"))
      (node (ref "D4") (pin "3") (pinfunction "3_3") (pintype "passive"))
      (node (ref "D5") (pin "3") (pinfunction "3_3") (pintype "passive"))
      (node (ref "D6") (pin "3") (pinfunction "3_3") (pintype "passive"))
      (node (ref "D7") (pin "3") (pinfunction "3_3") (pintype "passive"))
      (node (ref "D8") (pin "3") (pinfunction "3_3") (pintype "passive"))
      (node (ref "D9") (pin "3") (pinfunction "3_3") (pintype "passive"))
      (node (ref "J10") (pin "4") (pinfunction "4_4") (pintype "passive"))
      (node (ref "J11") (pin "1") (pinfunction "1_1") (pintype "passive"))
      (node (ref "J11") (pin "3") (pinfunction "3_3") (pintype "passive"))
      (node (ref "J2") (pin "A1/B12") (pinfunction "GND_A1/B12") (pintype "power_in"))
      (node (ref "J2") (pin "B1/A12") (pinfunction "GND_B1/A12") (pintype "power_in"))
      (node (ref "J2") (pin "S1") (pinfunction "SHIELD_S1") (pintype "passive"))
      (node (ref "J2") (pin "S2") (pinfunction "SHIELD_S2") (pintype "passive"))
      (node (ref "J2") (pin "S3") (pinfunction "SHIELD_S3") (pintype "passive"))
      (node (ref "J2") (pin "S4") (pinfunction "SHIELD_S4") (pintype "passive"))
      (node (ref "J3") (pin "4") (pinfunction "4_4") (pintype "passive"))
      (node (ref "J4") (pin "4") (pinfunction "4_4") (pintype "passive"))
      (node (ref "J5") (pin "4") (pinfunction "4_4") (pintype "passive"))
      (node (ref "J6") (pin "4") (pinfunction "4_4") (pintype "passive"))
      (node (ref "J7") (pin "4") (pinfunction "4_4") (pintype "passive"))
      (node (ref "J8") (pin "4") (pinfunction "4_4") (pintype "passive"))
      (node (ref "J9") (pin "4") (pinfunction "4_4") (pintype "passive"))
      (node (ref "R1") (pin "2") (pinfunction "2_2") (pintype "passive"))
      (node (ref "R10") (pin "2") (pinfunction "2_2") (pintype "passive"))
      (node (ref "R11") (pin "2") (pinfunction "2_2") (pintype "passive"))
      (node (ref "R16") (pin "2") (pinfunction "2_2") (pintype "passive"))
      (node (ref "R17") (pin "2") (pinfunction "2_2") (pintype "passive"))
      (node (ref "R18") (pin "2") (pinfunction "2_2") (pintype "passive"))
      (node (ref "R19") (pin "2") (pinfunction "2_2") (pintype "passive"))
      (node (ref "R20") (pin "1") (pinfunction "1_1") (pintype "passive"))
      (node (ref "R21") (pin "2") (pinfunction "2_2") (pintype "passive"))
      (node (ref "R22") (pin "1") (pinfunction "1_1") (pintype "passive"))
      (node (ref "R25") (pin "1") (pinfunction "1_1") (pintype "passive"))
      (node (ref "R8") (pin "2") (pinfunction "2_2") (pintype "passive"))
      (node (ref "R9") (pin "2") (pinfunction "2_2") (pintype "passive"))
      (node (ref "U1") (pin "20") (pinfunction "GND_20") (pintype "power_in"))
      (node (ref "U1") (pin "23") (pinfunction "GND_23") (pintype "power_in"))
      (node (ref "U1") (pin "35") (pinfunction "GND_35") (pintype "passive"))
      (node (ref "U1") (pin "47") (pinfunction "GND_47") (pintype "power_in"))
      (node (ref "U1") (pin "8") (pinfunction "GND_8") (pintype "power_in"))
      (node (ref "U2") (pin "1") (pinfunction "GND_1") (pintype "passive"))
      (node (ref "U3") (pin "1") (pinfunction "GND_1") (pintype "passive"))
    )
    (net (code "35") (name "Net-(D1-Pad1)") (class "Default")
      (node (ref "D1") (pin "1") (pinfunction "1_1") (pintype "passive"))
      (node (ref "R3") (pin "2") (pinfunction "2_2") (pintype "passive"))
    )
    (net (code "36") (name "Net-(J2-CC1)") (class "Default")
      (node (ref "J2") (pin "A5") (pinfunction "CC1_A5") (pintype "bidirectional"))
      (node (ref "R20") (pin "2") (pinfunction "2_2") (pintype "passive"))
    )
    (net (code "37") (name "Net-(J2-CC2)") (class "Default")
      (node (ref "J2") (pin "B5") (pinfunction "CC2_B5") (pintype "bidirectional"))
      (node (ref "R21") (pin "1") (pinfunction "1_1") (pintype "passive"))
    )
    (net (code "38") (name "Net-(U1-CFG)") (class "Default")
      (node (ref "R22") (pin "2") (pinfunction "2_2") (pintype "passive"))
      (node (ref "U1") (pin "2") (pinfunction "CFG_2") (pintype "passive"))
    )
    (net (code "39") (name "Net-(U1-TEST)") (class "Default")
      (node (ref "R1") (pin "1") (pinfunction "1_1") (pintype "passive"))
      (node (ref "U1") (pin "44") (pinfunction "TEST_44") (pintype "input"))
    )
    (net (code "40") (name "Net-(U1-XI)") (class "Default")
      (node (ref "C3") (pin "2") (pinfunction "2_2") (pintype "passive"))
      (node (ref "U1") (pin "5") (pinfunction "XI_5") (pintype "passive"))
      (node (ref "Y1") (pin "2") (pinfunction "2_2") (pintype "passive"))
    )
    (net (code "41") (name "Net-(U1-XO)") (class "Default")
      (node (ref "C6") (pin "2") (pinfunction "2_2") (pintype "passive"))
      (node (ref "U1") (pin "6") (pinfunction "XO_6") (pintype "passive"))
      (node (ref "Y1") (pin "1") (pinfunction "1_1") (pintype "passive"))
    )
    (net (code "42") (name "Net-(U3-ST)") (class "Default")
      (node (ref "R23") (pin "1") (pinfunction "1_1") (pintype "passive"))
      (node (ref "U3") (pin "8") (pinfunction "ST_8") (pintype "passive"))
    )
    (net (code "43") (name "Vin") (class "Default")
      (node (ref "J11") (pin "2") (pinfunction "2_2") (pintype "passive"))
      (node (ref "R23") (pin "2") (pinfunction "2_2") (pintype "passive"))
      (node (ref "R24") (pin "1") (pinfunction "1_1") (pintype "passive"))
      (node (ref "U3") (pin "3") (pinfunction "Vin1_3") (pintype "passive"))
      (node (ref "U3") (pin "5") (pinfunction "MODE_5") (pintype "passive"))
    )
    (net (code "44") (name "unconnected-(J2-SBU1-PadA8)") (class "Default")
      (node (ref "J2") (pin "A8") (pinfunction "SBU1_A8") (pintype "bidirectional+no_connect"))
    )
    (net (code "45") (name "unconnected-(J2-SBU2-PadB8)") (class "Default")
      (node (ref "J2") (pin "B8") (pinfunction "SBU2_B8") (pintype "bidirectional+no_connect"))
    )
    (net (code "46") (name "unconnected-(U1-ACT-Pad14)") (class "Default")
      (node (ref "U1") (pin "14") (pinfunction "ACT_14") (pintype "output+no_connect"))
    )
    (net (code "47") (name "unconnected-(U1-CTS0{slash}GPIO0-Pad32)") (class "Default")
      (node (ref "U1") (pin "32") (pinfunction "CTS0/GPIO0_32") (pintype "passive+no_connect"))
    )
    (net (code "48") (name "unconnected-(U1-CTS1{slash}GPIO2-Pad10)") (class "Default")
      (node (ref "U1") (pin "10") (pinfunction "CTS1/GPIO2_10") (pintype "passive+no_connect"))
    )
    (net (code "49") (name "unconnected-(U1-CTS2{slash}GPIO4-Pad26)") (class "Default")
      (node (ref "U1") (pin "26") (pinfunction "CTS2/GPIO4_26") (pintype "passive+no_connect"))
    )
    (net (code "50") (name "unconnected-(U1-CTS3{slash}GPIO6-Pad25)") (class "Default")
      (node (ref "U1") (pin "25") (pinfunction "CTS3/GPIO6_25") (pintype "passive+no_connect"))
    )
    (net (code "51") (name "unconnected-(U1-DTR0{slash}TNOW0{slash}GPIO8-Pad34)") (class "Default")
      (node (ref "U1") (pin "34") (pinfunction "DTR0/TNOW0/GPIO8_34") (pintype "bidirectional+no_connect"))
    )
    (net (code "52") (name "unconnected-(U1-DTR1{slash}TNOW1{slash}GPIO9-Pad15)") (class "Default")
      (node (ref "U1") (pin "15") (pinfunction "DTR1/TNOW1/GPIO9_15") (pintype "bidirectional+no_connect"))
    )
    (net (code "53") (name "unconnected-(U1-DTR2{slash}TN_O_W2{slash}GPIO10-Pad29)") (class "Default")
      (node (ref "U1") (pin "29") (pinfunction "DTR2/TN_O_W2/GPIO10_29") (pintype "bidirectional+no_connect"))
    )
    (net (code "54") (name "unconnected-(U1-DTR3{slash}TNOW3{slash}GPIO11-Pad39)") (class "Default")
      (node (ref "U1") (pin "39") (pinfunction "DTR3/TNOW3/GPIO11_39") (pintype "bidirectional"))
    )
    (net (code "55") (name "unconnected-(U1-NC-Pad1)") (class "Default")
      (node (ref "U1") (pin "1") (pinfunction "NC_1") (pintype "passive+no_connect"))
    )
    (net (code "56") (name "unconnected-(U1-NC-Pad3)") (class "Default")
      (node (ref "U1") (pin "3") (pinfunction "NC_3") (pintype "passive+no_connect"))
    )
    (net (code "57") (name "unconnected-(U1-NC-Pad4)") (class "Default")
      (node (ref "U1") (pin "4") (pinfunction "NC_4") (pintype "passive+no_connect"))
    )
    (net (code "58") (name "unconnected-(U1-RTS0{slash}GPIO1-Pad33)") (class "Default")
      (node (ref "U1") (pin "33") (pinfunction "RTS0/GPIO1_33") (pintype "output+no_connect"))
    )
    (net (code "59") (name "unconnected-(U1-RTS1{slash}GPIO3-Pad11)") (class "Default")
      (node (ref "U1") (pin "11") (pinfunction "RTS1/GPIO3_11") (pintype "output+no_connect"))
    )
    (net (code "60") (name "unconnected-(U1-RTS2{slash}GPIO5-Pad27)") (class "Default")
      (node (ref "U1") (pin "27") (pinfunction "RTS2/GPIO5_27") (pintype "output+no_connect"))
    )
    (net (code "61") (name "unconnected-(U1-RTS3{slash}GPIO7-Pad28)") (class "Default")
      (node (ref "U1") (pin "28") (pinfunction "RTS3/GPIO7_28") (pintype "output+no_connect"))
    )
  )
)
